# VFD_PSU.net
KiCad netlist of a schematic drawn in EAGLE
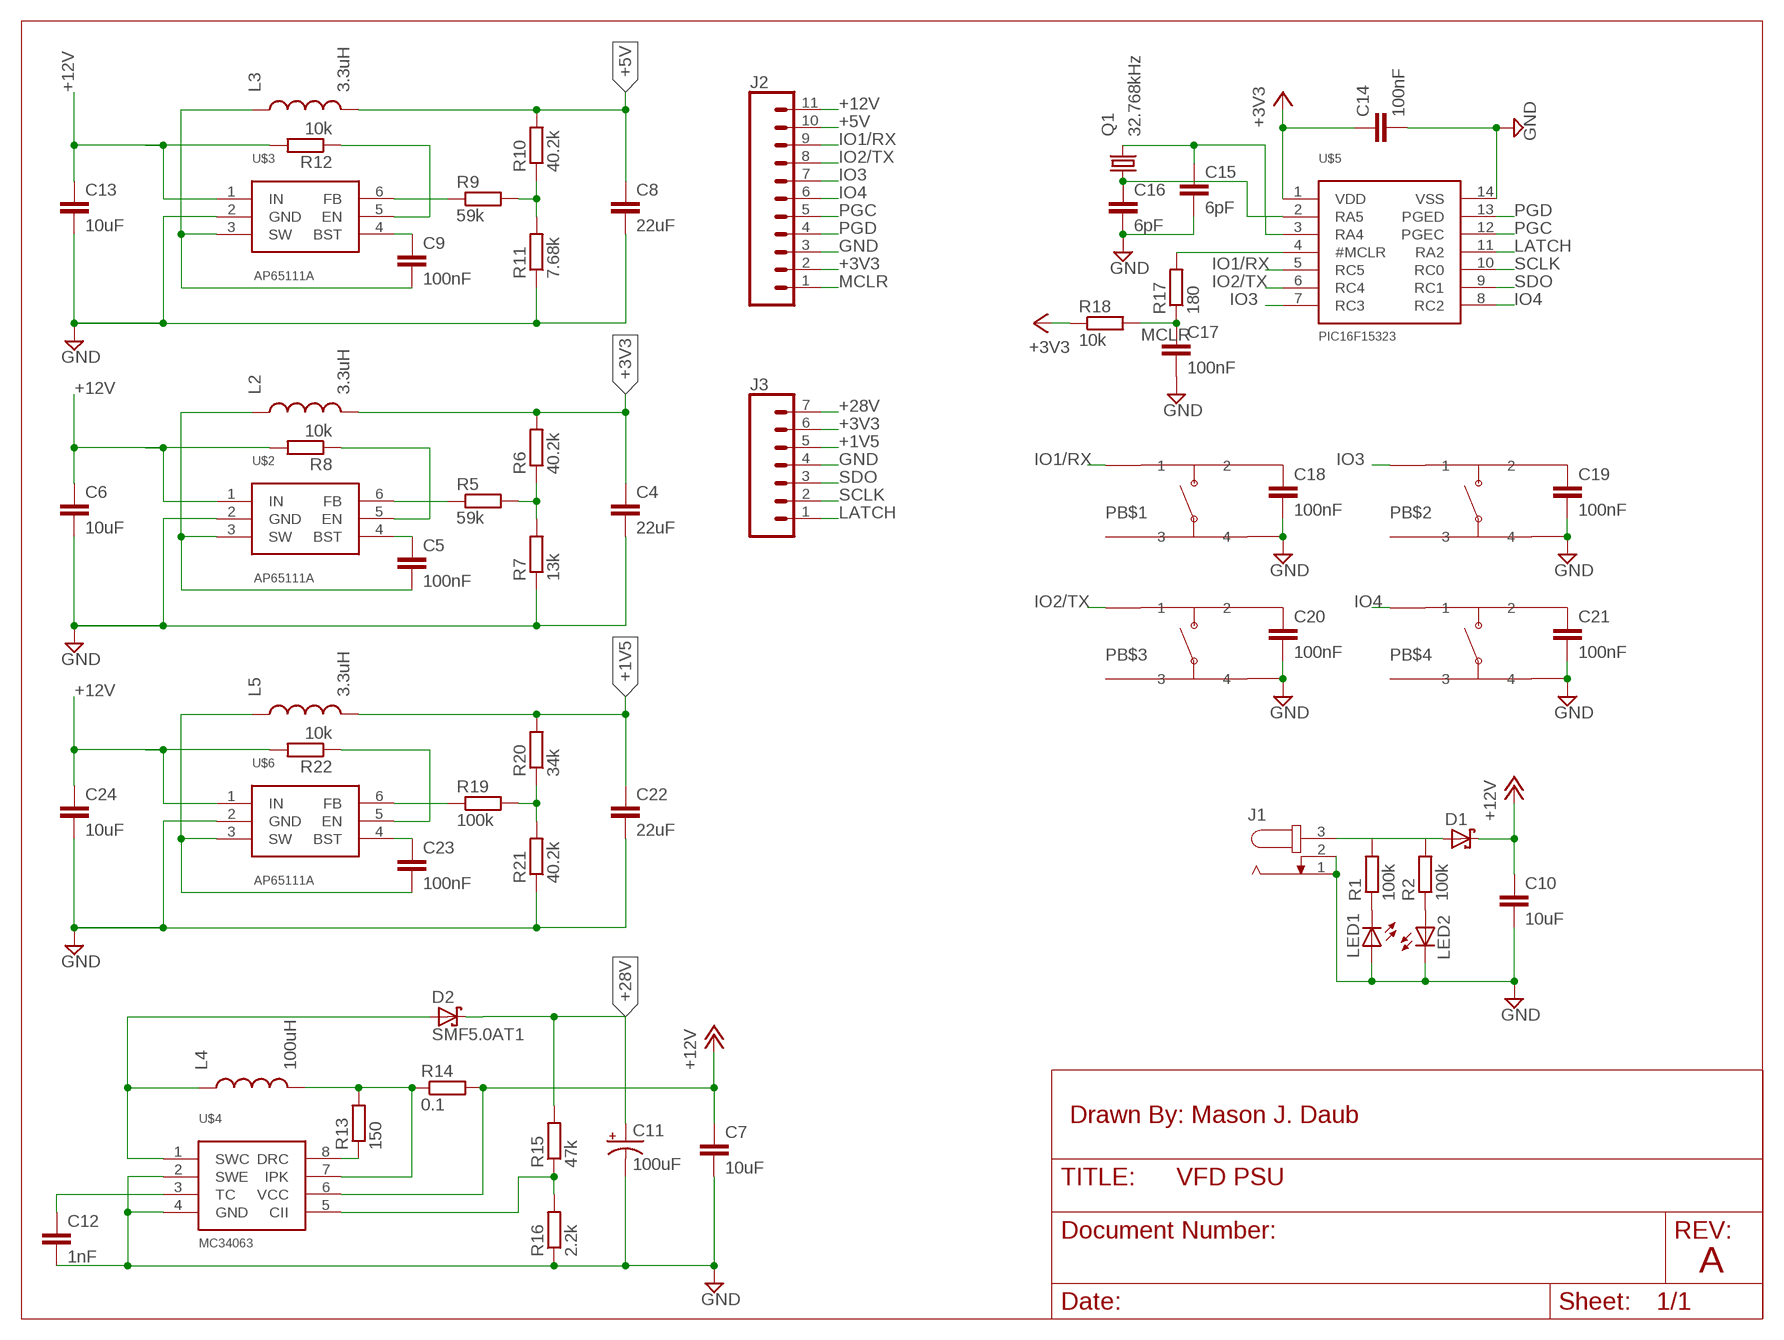
[diagram p0: schematic, sheet 1]

(export (version "E")
  (design (tool "Eeschema 10.0.6"))
  (components
    (comp (ref "C4")
      (value "22uF")
      (footprint "eagle-import:C0805")
      (libsource (lib "eagle-import") (part "C-EUC0805"))
    )
    (comp (ref "C5")
      (value "100nF")
      (footprint "eagle-import:C0603")
      (libsource (lib "eagle-import") (part "C-EUC0603"))
    )
    (comp (ref "C6")
      (value "10uF")
      (footprint "eagle-import:C0805")
      (libsource (lib "eagle-import") (part "C-EUC0805"))
    )
    (comp (ref "C7")
      (value "10uF")
      (footprint "eagle-import:C0805")
      (libsource (lib "eagle-import") (part "C-EUC0805"))
    )
    (comp (ref "C8")
      (value "22uF")
      (footprint "eagle-import:C0805")
      (libsource (lib "eagle-import") (part "C-EUC0805"))
    )
    (comp (ref "C9")
      (value "100nF")
      (footprint "eagle-import:C0603")
      (libsource (lib "eagle-import") (part "C-EUC0603"))
    )
    (comp (ref "C10")
      (value "10uF")
      (footprint "eagle-import:C0805")
      (libsource (lib "eagle-import") (part "C-EUC0805"))
    )
    (comp (ref "C11")
      (value "100uF")
      (footprint "eagle-import:PANASONIC_C")
      (libsource (lib "eagle-import") (part "22UF-POLAR-PANASONIC_C-35V-20%"))
    )
    (comp (ref "C12")
      (value "1nF")
      (footprint "eagle-import:C0603")
      (libsource (lib "eagle-import") (part "C-EUC0603"))
    )
    (comp (ref "C13")
      (value "10uF")
      (footprint "eagle-import:C0805")
      (libsource (lib "eagle-import") (part "C-EUC0805"))
    )
    (comp (ref "C14")
      (value "100nF")
      (footprint "eagle-import:C0603")
      (libsource (lib "eagle-import") (part "C-EUC0603"))
    )
    (comp (ref "C15")
      (value "6pF")
      (footprint "eagle-import:C0603")
      (libsource (lib "eagle-import") (part "C-EUC0603"))
    )
    (comp (ref "C16")
      (value "6pF")
      (footprint "eagle-import:C0603")
      (libsource (lib "eagle-import") (part "C-EUC0603"))
    )
    (comp (ref "C17")
      (value "100nF")
      (footprint "eagle-import:C0603")
      (libsource (lib "eagle-import") (part "C-EUC0603"))
    )
    (comp (ref "C18")
      (value "100nF")
      (footprint "eagle-import:C0603")
      (libsource (lib "eagle-import") (part "C-EUC0603"))
    )
    (comp (ref "C19")
      (value "100nF")
      (footprint "eagle-import:C0603")
      (libsource (lib "eagle-import") (part "C-EUC0603"))
    )
    (comp (ref "C20")
      (value "100nF")
      (footprint "eagle-import:C0603")
      (libsource (lib "eagle-import") (part "C-EUC0603"))
    )
    (comp (ref "C21")
      (value "100nF")
      (footprint "eagle-import:C0603")
      (libsource (lib "eagle-import") (part "C-EUC0603"))
    )
    (comp (ref "C22")
      (value "22uF")
      (footprint "eagle-import:C0805")
      (libsource (lib "eagle-import") (part "C-EUC0805"))
    )
    (comp (ref "C23")
      (value "100nF")
      (footprint "eagle-import:C0603")
      (libsource (lib "eagle-import") (part "C-EUC0603"))
    )
    (comp (ref "C24")
      (value "10uF")
      (footprint "eagle-import:C0805")
      (libsource (lib "eagle-import") (part "C-EUC0805"))
    )
    (comp (ref "D1")
      (value "SCHOTTKY-DIODESMD")
      (footprint "eagle-import:SMB")
      (libsource (lib "eagle-import") (part "SCHOTTKY-DIODESMD"))
    )
    (comp (ref "D2")
      (value "SMF5.0AT1")
      (footprint "eagle-import:SOD123FL")
      (libsource (lib "eagle-import") (part "SMF5.0AT1"))
    )
    (comp (ref "J1")
      (value "JACK-PLUG0")
      (footprint "eagle-import:SPC4077")
      (libsource (lib "eagle-import") (part "JACK-PLUG0"))
    )
    (comp (ref "J2")
      (value "CONN_111X11_NO_SILK")
      (footprint "eagle-import:1X11_NO_SILK")
      (libsource (lib "eagle-import") (part "CONN_111X11_NO_SILK"))
    )
    (comp (ref "J3")
      (value "CONN_07LONGPADS")
      (footprint "eagle-import:1X07_LONGPADS")
      (libsource (lib "eagle-import") (part "CONN_07LONGPADS"))
    )
    (comp (ref "L2")
      (value "3.3uH")
      (footprint "eagle-import:1008")
      (libsource (lib "eagle-import") (part "L1008"))
    )
    (comp (ref "L3")
      (value "3.3uH")
      (footprint "eagle-import:1008")
      (libsource (lib "eagle-import") (part "L1008"))
    )
    (comp (ref "L4")
      (value "100uH")
      (footprint "eagle-import:2-SMD")
      (libsource (lib "eagle-import") (part "ETQ-P5M101YGK"))
    )
    (comp (ref "L5")
      (value "3.3uH")
      (footprint "eagle-import:1008")
      (libsource (lib "eagle-import") (part "L1008"))
    )
    (comp (ref "LED1")
      (value "LEDSMT1206")
      (footprint "eagle-import:1206")
      (libsource (lib "eagle-import") (part "LEDSMT1206"))
    )
    (comp (ref "LED2")
      (value "LEDSMT1206")
      (footprint "eagle-import:1206")
      (libsource (lib "eagle-import") (part "LEDSMT1206"))
    )
    (comp (ref "PB$1")
      (value "PTS645SM43SMTR92-LFS")
      (footprint "eagle-import:SMDTACTILE")
      (libsource (lib "eagle-import") (part "PTS645SM43SMTR92-LFS"))
    )
    (comp (ref "PB$2")
      (value "PTS645SM43SMTR92-LFS")
      (footprint "eagle-import:SMDTACTILE")
      (libsource (lib "eagle-import") (part "PTS645SM43SMTR92-LFS"))
    )
    (comp (ref "PB$3")
      (value "PTS645SM43SMTR92-LFS")
      (footprint "eagle-import:SMDTACTILE")
      (libsource (lib "eagle-import") (part "PTS645SM43SMTR92-LFS"))
    )
    (comp (ref "PB$4")
      (value "PTS645SM43SMTR92-LFS")
      (footprint "eagle-import:SMDTACTILE")
      (libsource (lib "eagle-import") (part "PTS645SM43SMTR92-LFS"))
    )
    (comp (ref "Q1")
      (value "32.768kHz")
      (footprint "eagle-import:8.2X3.8")
      (libsource (lib "eagle-import") (part "KX-327-S"))
    )
    (comp (ref "R1")
      (value "100k")
      (footprint "eagle-import:R0603")
      (libsource (lib "eagle-import") (part "resistor_348_R-EU_R0603"))
    )
    (comp (ref "R2")
      (value "100k")
      (footprint "eagle-import:R0603")
      (libsource (lib "eagle-import") (part "resistor_348_R-EU_R0603"))
    )
    (comp (ref "R5")
      (value "59k")
      (footprint "eagle-import:R0603")
      (libsource (lib "eagle-import") (part "resistor_348_R-EU_R0603"))
    )
    (comp (ref "R6")
      (value "40.2k")
      (footprint "eagle-import:R0603")
      (libsource (lib "eagle-import") (part "resistor_348_R-EU_R0603"))
    )
    (comp (ref "R7")
      (value "13k")
      (footprint "eagle-import:R0603")
      (libsource (lib "eagle-import") (part "resistor_348_R-EU_R0603"))
    )
    (comp (ref "R8")
      (value "10k")
      (footprint "eagle-import:R0603")
      (libsource (lib "eagle-import") (part "resistor_348_R-EU_R0603"))
    )
    (comp (ref "R9")
      (value "59k")
      (footprint "eagle-import:R0603")
      (libsource (lib "eagle-import") (part "resistor_348_R-EU_R0603"))
    )
    (comp (ref "R10")
      (value "40.2k")
      (footprint "eagle-import:R0603")
      (libsource (lib "eagle-import") (part "resistor_348_R-EU_R0603"))
    )
    (comp (ref "R11")
      (value "7.68k")
      (footprint "eagle-import:R0603")
      (libsource (lib "eagle-import") (part "resistor_348_R-EU_R0603"))
    )
    (comp (ref "R12")
      (value "10k")
      (footprint "eagle-import:R0603")
      (libsource (lib "eagle-import") (part "resistor_348_R-EU_R0603"))
    )
    (comp (ref "R13")
      (value "150")
      (footprint "eagle-import:R0603")
      (libsource (lib "eagle-import") (part "resistor_348_R-EU_R0603"))
    )
    (comp (ref "R14")
      (value "0.1")
      (footprint "eagle-import:R0805")
      (libsource (lib "eagle-import") (part "R-EU_R0805"))
    )
    (comp (ref "R15")
      (value "47k")
      (footprint "eagle-import:R0603")
      (libsource (lib "eagle-import") (part "resistor_348_R-EU_R0603"))
    )
    (comp (ref "R16")
      (value "2.2k")
      (footprint "eagle-import:R0603")
      (libsource (lib "eagle-import") (part "resistor_348_R-EU_R0603"))
    )
    (comp (ref "R17")
      (value "180")
      (footprint "eagle-import:R0603")
      (libsource (lib "eagle-import") (part "resistor_348_R-EU_R0603"))
    )
    (comp (ref "R18")
      (value "10k")
      (footprint "eagle-import:R0603")
      (libsource (lib "eagle-import") (part "resistor_348_R-EU_R0603"))
    )
    (comp (ref "R19")
      (value "100k")
      (footprint "eagle-import:R0603")
      (libsource (lib "eagle-import") (part "resistor_348_R-EU_R0603"))
    )
    (comp (ref "R20")
      (value "34k")
      (footprint "eagle-import:R0603")
      (libsource (lib "eagle-import") (part "resistor_348_R-EU_R0603"))
    )
    (comp (ref "R21")
      (value "40.2k")
      (footprint "eagle-import:R0603")
      (libsource (lib "eagle-import") (part "resistor_348_R-EU_R0603"))
    )
    (comp (ref "R22")
      (value "10k")
      (footprint "eagle-import:R0603")
      (libsource (lib "eagle-import") (part "resistor_348_R-EU_R0603"))
    )
    (comp (ref "U$2")
      (value "AP65111A")
      (footprint "eagle-import:TSOT23-6")
      (libsource (lib "eagle-import") (part "AP65111A"))
    )
    (comp (ref "U$3")
      (value "AP65111A")
      (footprint "eagle-import:TSOT23-6")
      (libsource (lib "eagle-import") (part "AP65111A"))
    )
    (comp (ref "U$4")
      (value "MC34063")
      (footprint "eagle-import:SO08")
      (libsource (lib "eagle-import") (part "MC34063"))
    )
    (comp (ref "U$5")
      (value "PIC16F15323")
      (footprint "eagle-import:SO14")
      (libsource (lib "eagle-import") (part "PIC16F15323"))
    )
    (comp (ref "U$6")
      (value "AP65111A")
      (footprint "eagle-import:TSOT23-6")
      (libsource (lib "eagle-import") (part "AP65111A"))
    )
  )
  (nets
    (net (code "1") (name "+1V5") (class "Default")
      (node (ref "C22") (pin "1") (pinfunction "1_1") (pintype "passive"))
      (node (ref "J3") (pin "5") (pinfunction "5_5") (pintype "passive"))
      (node (ref "L5") (pin "P$2") (pinfunction "2_P$2") (pintype "passive"))
      (node (ref "R20") (pin "2") (pinfunction "2_2") (pintype "passive"))
    )
    (net (code "2") (name "+3V3") (class "Default")
      (node (ref "C14") (pin "1") (pinfunction "1_1") (pintype "passive"))
      (node (ref "C4") (pin "1") (pinfunction "1_1") (pintype "passive"))
      (node (ref "J2") (pin "2") (pinfunction "2_2") (pintype "passive"))
      (node (ref "J3") (pin "6") (pinfunction "6_6") (pintype "passive"))
      (node (ref "L2") (pin "P$2") (pinfunction "2_P$2") (pintype "passive"))
      (node (ref "R18") (pin "1") (pinfunction "1_1") (pintype "passive"))
      (node (ref "R6") (pin "2") (pinfunction "2_2") (pintype "passive"))
      (node (ref "U$5") (pin "1") (pinfunction "VDD_1") (pintype "bidirectional"))
    )
    (net (code "3") (name "+5V") (class "Default")
      (node (ref "C8") (pin "1") (pinfunction "1_1") (pintype "passive"))
      (node (ref "J2") (pin "10") (pinfunction "10_10") (pintype "passive"))
      (node (ref "L3") (pin "P$2") (pinfunction "2_P$2") (pintype "passive"))
      (node (ref "R10") (pin "2") (pinfunction "2_2") (pintype "passive"))
    )
    (net (code "4") (name "+12V") (class "Default")
      (node (ref "C10") (pin "1") (pinfunction "1_1") (pintype "passive"))
      (node (ref "C13") (pin "1") (pinfunction "1_1") (pintype "passive"))
      (node (ref "C24") (pin "1") (pinfunction "1_1") (pintype "passive"))
      (node (ref "C6") (pin "1") (pinfunction "1_1") (pintype "passive"))
      (node (ref "C7") (pin "1") (pinfunction "1_1") (pintype "passive"))
      (node (ref "D1") (pin "C") (pinfunction "C_C") (pintype "passive"))
      (node (ref "J2") (pin "11") (pinfunction "11_11") (pintype "passive"))
      (node (ref "R12") (pin "2") (pinfunction "2_2") (pintype "passive"))
      (node (ref "R14") (pin "2") (pinfunction "2_2") (pintype "passive"))
      (node (ref "R22") (pin "2") (pinfunction "2_2") (pintype "passive"))
      (node (ref "R8") (pin "2") (pinfunction "2_2") (pintype "passive"))
      (node (ref "U$2") (pin "1") (pinfunction "IN_1") (pintype "bidirectional"))
      (node (ref "U$3") (pin "1") (pinfunction "IN_1") (pintype "bidirectional"))
      (node (ref "U$4") (pin "6") (pinfunction "VCC_6") (pintype "bidirectional"))
      (node (ref "U$6") (pin "1") (pinfunction "IN_1") (pintype "bidirectional"))
    )
    (net (code "5") (name "+28V") (class "Default")
      (node (ref "C11") (pin "+") (pinfunction "+_+") (pintype "passive"))
      (node (ref "D2") (pin "C") (pinfunction "C_C") (pintype "passive"))
      (node (ref "J3") (pin "7") (pinfunction "7_7") (pintype "passive"))
      (node (ref "R15") (pin "2") (pinfunction "2_2") (pintype "passive"))
    )
    (net (code "6") (name "/IO1{slash}RX") (class "Default")
      (node (ref "J2") (pin "9") (pinfunction "9_9") (pintype "passive"))
      (node (ref "PB$1") (pin "P$1") (pinfunction "1_P$1") (pintype "bidirectional"))
      (node (ref "U$5") (pin "5") (pinfunction "RC5_5") (pintype "bidirectional"))
    )
    (net (code "7") (name "/IO2{slash}TX") (class "Default")
      (node (ref "J2") (pin "8") (pinfunction "8_8") (pintype "passive"))
      (node (ref "PB$3") (pin "P$1") (pinfunction "1_P$1") (pintype "bidirectional"))
      (node (ref "U$5") (pin "6") (pinfunction "RC4_6") (pintype "bidirectional"))
    )
    (net (code "8") (name "/IO3") (class "Default")
      (node (ref "J2") (pin "7") (pinfunction "7_7") (pintype "passive"))
      (node (ref "PB$2") (pin "P$1") (pinfunction "1_P$1") (pintype "bidirectional"))
      (node (ref "U$5") (pin "7") (pinfunction "RC3_7") (pintype "bidirectional"))
    )
    (net (code "9") (name "/IO4") (class "Default")
      (node (ref "J2") (pin "6") (pinfunction "6_6") (pintype "passive"))
      (node (ref "PB$4") (pin "P$1") (pinfunction "1_P$1") (pintype "bidirectional"))
      (node (ref "U$5") (pin "8") (pinfunction "RC2_8") (pintype "bidirectional"))
    )
    (net (code "10") (name "/LATCH") (class "Default")
      (node (ref "J3") (pin "1") (pinfunction "1_1") (pintype "passive"))
      (node (ref "U$5") (pin "11") (pinfunction "RA2_11") (pintype "bidirectional"))
    )
    (net (code "11") (name "/MCLR") (class "Default")
      (node (ref "C17") (pin "1") (pinfunction "1_1") (pintype "passive"))
      (node (ref "J2") (pin "1") (pinfunction "1_1") (pintype "passive"))
      (node (ref "R17") (pin "1") (pinfunction "1_1") (pintype "passive"))
      (node (ref "R18") (pin "2") (pinfunction "2_2") (pintype "passive"))
    )
    (net (code "12") (name "/PGC") (class "Default")
      (node (ref "J2") (pin "5") (pinfunction "5_5") (pintype "passive"))
      (node (ref "U$5") (pin "12") (pinfunction "PGEC_12") (pintype "bidirectional"))
    )
    (net (code "13") (name "/PGD") (class "Default")
      (node (ref "J2") (pin "4") (pinfunction "4_4") (pintype "passive"))
      (node (ref "U$5") (pin "13") (pinfunction "PGED_13") (pintype "bidirectional"))
    )
    (net (code "14") (name "/SCLK") (class "Default")
      (node (ref "J3") (pin "2") (pinfunction "2_2") (pintype "passive"))
      (node (ref "U$5") (pin "10") (pinfunction "RC0_10") (pintype "bidirectional"))
    )
    (net (code "15") (name "/SDO") (class "Default")
      (node (ref "J3") (pin "3") (pinfunction "3_3") (pintype "passive"))
      (node (ref "U$5") (pin "9") (pinfunction "RC1_9") (pintype "bidirectional"))
    )
    (net (code "16") (name "GND") (class "Default")
      (node (ref "C10") (pin "2") (pinfunction "2_2") (pintype "passive"))
      (node (ref "C11") (pin "-") (pinfunction "-_-") (pintype "passive"))
      (node (ref "C12") (pin "2") (pinfunction "2_2") (pintype "passive"))
      (node (ref "C13") (pin "2") (pinfunction "2_2") (pintype "passive"))
      (node (ref "C14") (pin "2") (pinfunction "2_2") (pintype "passive"))
      (node (ref "C15") (pin "2") (pinfunction "2_2") (pintype "passive"))
      (node (ref "C16") (pin "2") (pinfunction "2_2") (pintype "passive"))
      (node (ref "C17") (pin "2") (pinfunction "2_2") (pintype "passive"))
      (node (ref "C18") (pin "2") (pinfunction "2_2") (pintype "passive"))
      (node (ref "C19") (pin "2") (pinfunction "2_2") (pintype "passive"))
      (node (ref "C20") (pin "2") (pinfunction "2_2") (pintype "passive"))
      (node (ref "C21") (pin "2") (pinfunction "2_2") (pintype "passive"))
      (node (ref "C22") (pin "2") (pinfunction "2_2") (pintype "passive"))
      (node (ref "C24") (pin "2") (pinfunction "2_2") (pintype "passive"))
      (node (ref "C4") (pin "2") (pinfunction "2_2") (pintype "passive"))
      (node (ref "C6") (pin "2") (pinfunction "2_2") (pintype "passive"))
      (node (ref "C7") (pin "2") (pinfunction "2_2") (pintype "passive"))
      (node (ref "C8") (pin "2") (pinfunction "2_2") (pintype "passive"))
      (node (ref "J1") (pin "1") (pinfunction "1_1") (pintype "passive"))
      (node (ref "J1") (pin "2") (pinfunction "2_2") (pintype "passive"))
      (node (ref "J2") (pin "3") (pinfunction "3_3") (pintype "passive"))
      (node (ref "J3") (pin "4") (pinfunction "4_4") (pintype "passive"))
      (node (ref "LED1") (pin "A") (pinfunction "A_A") (pintype "passive"))
      (node (ref "LED2") (pin "C") (pinfunction "C_C") (pintype "passive"))
      (node (ref "PB$1") (pin "P$4") (pinfunction "4_P$4") (pintype "bidirectional"))
      (node (ref "PB$2") (pin "P$4") (pinfunction "4_P$4") (pintype "bidirectional"))
      (node (ref "PB$3") (pin "P$4") (pinfunction "4_P$4") (pintype "bidirectional"))
      (node (ref "PB$4") (pin "P$4") (pinfunction "4_P$4") (pintype "bidirectional"))
      (node (ref "R11") (pin "1") (pinfunction "1_1") (pintype "passive"))
      (node (ref "R16") (pin "1") (pinfunction "1_1") (pintype "passive"))
      (node (ref "R21") (pin "1") (pinfunction "1_1") (pintype "passive"))
      (node (ref "R7") (pin "1") (pinfunction "1_1") (pintype "passive"))
      (node (ref "U$2") (pin "2") (pinfunction "GND_2") (pintype "bidirectional"))
      (node (ref "U$3") (pin "2") (pinfunction "GND_2") (pintype "bidirectional"))
      (node (ref "U$4") (pin "2") (pinfunction "SWE_2") (pintype "bidirectional"))
      (node (ref "U$4") (pin "4") (pinfunction "GND_4") (pintype "bidirectional"))
      (node (ref "U$5") (pin "14") (pinfunction "VSS_14") (pintype "bidirectional"))
      (node (ref "U$6") (pin "2") (pinfunction "GND_2") (pintype "bidirectional"))
    )
    (net (code "17") (name "Net-(D1-PadA)") (class "Default")
      (node (ref "D1") (pin "A") (pinfunction "A_A") (pintype "passive"))
      (node (ref "J1") (pin "3") (pinfunction "3_3") (pintype "passive"))
      (node (ref "R1") (pin "2") (pinfunction "2_2") (pintype "passive"))
      (node (ref "R2") (pin "2") (pinfunction "2_2") (pintype "passive"))
    )
    (net (code "18") (name "Net-(L2-1)") (class "Default")
      (node (ref "C5") (pin "2") (pinfunction "2_2") (pintype "passive"))
      (node (ref "L2") (pin "P$1") (pinfunction "1_P$1") (pintype "passive"))
      (node (ref "U$2") (pin "3") (pinfunction "SW_3") (pintype "bidirectional"))
    )
    (net (code "19") (name "Net-(L3-1)") (class "Default")
      (node (ref "C9") (pin "2") (pinfunction "2_2") (pintype "passive"))
      (node (ref "L3") (pin "P$1") (pinfunction "1_P$1") (pintype "passive"))
      (node (ref "U$3") (pin "3") (pinfunction "SW_3") (pintype "bidirectional"))
    )
    (net (code "20") (name "Net-(L4-1)") (class "Default")
      (node (ref "D2") (pin "A") (pinfunction "A_A") (pintype "passive"))
      (node (ref "L4") (pin "P$1") (pinfunction "1_P$1") (pintype "passive"))
      (node (ref "U$4") (pin "1") (pinfunction "SWC_1") (pintype "bidirectional"))
    )
    (net (code "21") (name "Net-(L4-2)") (class "Default")
      (node (ref "L4") (pin "P$2") (pinfunction "2_P$2") (pintype "passive"))
      (node (ref "R13") (pin "2") (pinfunction "2_2") (pintype "passive"))
      (node (ref "R14") (pin "1") (pinfunction "1_1") (pintype "passive"))
      (node (ref "U$4") (pin "7") (pinfunction "IPK_7") (pintype "bidirectional"))
    )
    (net (code "22") (name "Net-(L5-1)") (class "Default")
      (node (ref "C23") (pin "2") (pinfunction "2_2") (pintype "passive"))
      (node (ref "L5") (pin "P$1") (pinfunction "1_P$1") (pintype "passive"))
      (node (ref "U$6") (pin "3") (pinfunction "SW_3") (pintype "bidirectional"))
    )
    (net (code "23") (name "Net-(LED1-PadC)") (class "Default")
      (node (ref "LED1") (pin "C") (pinfunction "C_C") (pintype "passive"))
      (node (ref "R1") (pin "1") (pinfunction "1_1") (pintype "passive"))
    )
    (net (code "24") (name "Net-(LED2-PadA)") (class "Default")
      (node (ref "LED2") (pin "A") (pinfunction "A_A") (pintype "passive"))
      (node (ref "R2") (pin "1") (pinfunction "1_1") (pintype "passive"))
    )
    (net (code "25") (name "Net-(PB$1-2)") (class "Default")
      (node (ref "C18") (pin "1") (pinfunction "1_1") (pintype "passive"))
      (node (ref "PB$1") (pin "P$2") (pinfunction "2_P$2") (pintype "bidirectional"))
    )
    (net (code "26") (name "Net-(PB$2-2)") (class "Default")
      (node (ref "C19") (pin "1") (pinfunction "1_1") (pintype "passive"))
      (node (ref "PB$2") (pin "P$2") (pinfunction "2_P$2") (pintype "bidirectional"))
    )
    (net (code "27") (name "Net-(PB$3-2)") (class "Default")
      (node (ref "C20") (pin "1") (pinfunction "1_1") (pintype "passive"))
      (node (ref "PB$3") (pin "P$2") (pinfunction "2_P$2") (pintype "bidirectional"))
    )
    (net (code "28") (name "Net-(PB$4-2)") (class "Default")
      (node (ref "C21") (pin "1") (pinfunction "1_1") (pintype "passive"))
      (node (ref "PB$4") (pin "P$2") (pinfunction "2_P$2") (pintype "bidirectional"))
    )
    (net (code "29") (name "Net-(Q1-2)") (class "Default")
      (node (ref "C15") (pin "1") (pinfunction "1_1") (pintype "passive"))
      (node (ref "Q1") (pin "4") (pinfunction "2_4") (pintype "passive"))
      (node (ref "U$5") (pin "3") (pinfunction "RA4_3") (pintype "bidirectional"))
    )
    (net (code "30") (name "Net-(R5-Pad2)") (class "Default")
      (node (ref "R5") (pin "2") (pinfunction "2_2") (pintype "passive"))
      (node (ref "R6") (pin "1") (pinfunction "1_1") (pintype "passive"))
      (node (ref "R7") (pin "2") (pinfunction "2_2") (pintype "passive"))
    )
    (net (code "31") (name "Net-(R10-Pad1)") (class "Default")
      (node (ref "R10") (pin "1") (pinfunction "1_1") (pintype "passive"))
      (node (ref "R11") (pin "2") (pinfunction "2_2") (pintype "passive"))
      (node (ref "R9") (pin "2") (pinfunction "2_2") (pintype "passive"))
    )
    (net (code "32") (name "Net-(R19-Pad2)") (class "Default")
      (node (ref "R19") (pin "2") (pinfunction "2_2") (pintype "passive"))
      (node (ref "R20") (pin "1") (pinfunction "1_1") (pintype "passive"))
      (node (ref "R21") (pin "2") (pinfunction "2_2") (pintype "passive"))
    )
    (net (code "33") (name "Net-(U$2-BST)") (class "Default")
      (node (ref "C5") (pin "1") (pinfunction "1_1") (pintype "passive"))
      (node (ref "U$2") (pin "4") (pinfunction "BST_4") (pintype "bidirectional"))
    )
    (net (code "34") (name "Net-(U$2-EN)") (class "Default")
      (node (ref "R8") (pin "1") (pinfunction "1_1") (pintype "passive"))
      (node (ref "U$2") (pin "5") (pinfunction "EN_5") (pintype "bidirectional"))
    )
    (net (code "35") (name "Net-(U$2-FB)") (class "Default")
      (node (ref "R5") (pin "1") (pinfunction "1_1") (pintype "passive"))
      (node (ref "U$2") (pin "6") (pinfunction "FB_6") (pintype "bidirectional"))
    )
    (net (code "36") (name "Net-(U$3-BST)") (class "Default")
      (node (ref "C9") (pin "1") (pinfunction "1_1") (pintype "passive"))
      (node (ref "U$3") (pin "4") (pinfunction "BST_4") (pintype "bidirectional"))
    )
    (net (code "37") (name "Net-(U$3-EN)") (class "Default")
      (node (ref "R12") (pin "1") (pinfunction "1_1") (pintype "passive"))
      (node (ref "U$3") (pin "5") (pinfunction "EN_5") (pintype "bidirectional"))
    )
    (net (code "38") (name "Net-(U$3-FB)") (class "Default")
      (node (ref "R9") (pin "1") (pinfunction "1_1") (pintype "passive"))
      (node (ref "U$3") (pin "6") (pinfunction "FB_6") (pintype "bidirectional"))
    )
    (net (code "39") (name "Net-(U$4-CII)") (class "Default")
      (node (ref "R15") (pin "1") (pinfunction "1_1") (pintype "passive"))
      (node (ref "R16") (pin "2") (pinfunction "2_2") (pintype "passive"))
      (node (ref "U$4") (pin "5") (pinfunction "CII_5") (pintype "bidirectional"))
    )
    (net (code "40") (name "Net-(U$4-DRC)") (class "Default")
      (node (ref "R13") (pin "1") (pinfunction "1_1") (pintype "passive"))
      (node (ref "U$4") (pin "8") (pinfunction "DRC_8") (pintype "bidirectional"))
    )
    (net (code "41") (name "Net-(U$4-TC)") (class "Default")
      (node (ref "C12") (pin "1") (pinfunction "1_1") (pintype "passive"))
      (node (ref "U$4") (pin "3") (pinfunction "TC_3") (pintype "bidirectional"))
    )
    (net (code "42") (name "Net-(U$5-#MCLR)") (class "Default")
      (node (ref "R17") (pin "2") (pinfunction "2_2") (pintype "passive"))
      (node (ref "U$5") (pin "4") (pinfunction "#MCLR_4") (pintype "bidirectional"))
    )
    (net (code "43") (name "Net-(U$5-RA5)") (class "Default")
      (node (ref "C16") (pin "1") (pinfunction "1_1") (pintype "passive"))
      (node (ref "Q1") (pin "1") (pinfunction "1_1") (pintype "passive"))
      (node (ref "U$5") (pin "2") (pinfunction "RA5_2") (pintype "bidirectional"))
    )
    (net (code "44") (name "Net-(U$6-BST)") (class "Default")
      (node (ref "C23") (pin "1") (pinfunction "1_1") (pintype "passive"))
      (node (ref "U$6") (pin "4") (pinfunction "BST_4") (pintype "bidirectional"))
    )
    (net (code "45") (name "Net-(U$6-EN)") (class "Default")
      (node (ref "R22") (pin "1") (pinfunction "1_1") (pintype "passive"))
      (node (ref "U$6") (pin "5") (pinfunction "EN_5") (pintype "bidirectional"))
    )
    (net (code "46") (name "Net-(U$6-FB)") (class "Default")
      (node (ref "R19") (pin "1") (pinfunction "1_1") (pintype "passive"))
      (node (ref "U$6") (pin "6") (pinfunction "FB_6") (pintype "bidirectional"))
    )
    (net (code "47") (name "unconnected-(PB$1-3-PadP$3)") (class "Default")
      (node (ref "PB$1") (pin "P$3") (pinfunction "3_P$3") (pintype "bidirectional"))
    )
    (net (code "48") (name "unconnected-(PB$2-3-PadP$3)") (class "Default")
      (node (ref "PB$2") (pin "P$3") (pinfunction "3_P$3") (pintype "bidirectional"))
    )
    (net (code "49") (name "unconnected-(PB$3-3-PadP$3)") (class "Default")
      (node (ref "PB$3") (pin "P$3") (pinfunction "3_P$3") (pintype "bidirectional"))
    )
    (net (code "50") (name "unconnected-(PB$4-3-PadP$3)") (class "Default")
      (node (ref "PB$4") (pin "P$3") (pinfunction "3_P$3") (pintype "bidirectional"))
    )
  )
)
